# 2_ext_conn.net
KiCad netlist of a schematic drawn in Altium Designer
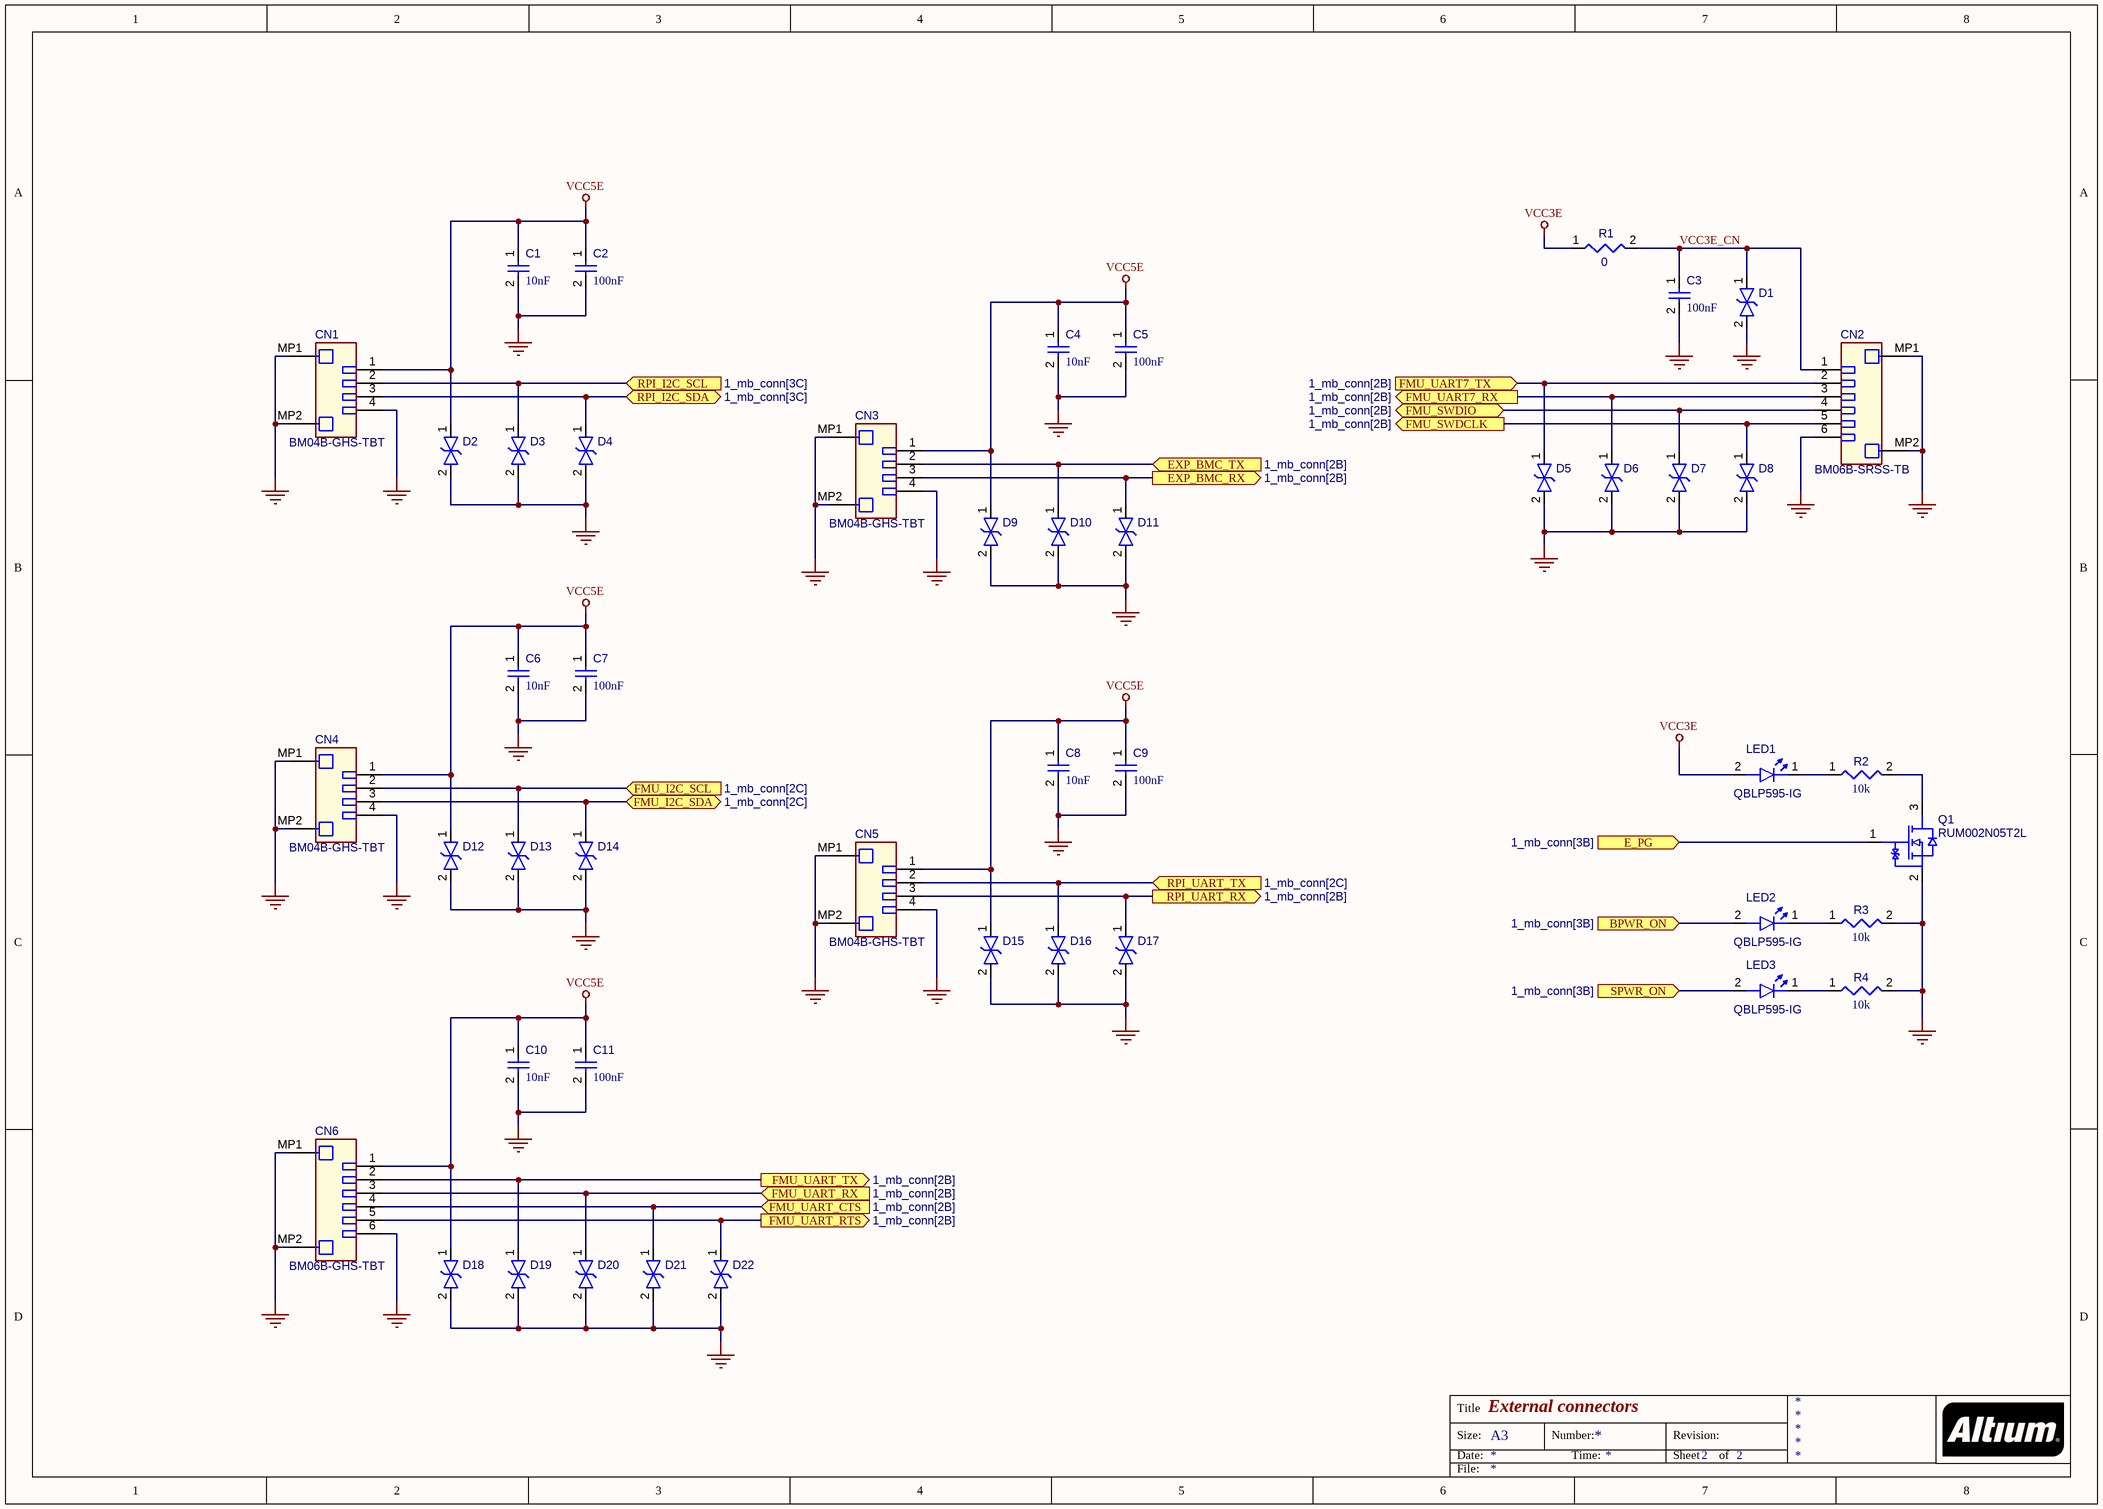
[diagram p0: 2_ext_conn.SchDoc]

(export (version "E")
  (design (tool "Eeschema 10.0.6"))
  (components
    (comp (ref "C1")
      (value "10nF")
      (footprint "CAPC0402(1005)60_L")
      (description "Chip Capacitor, 10nF +/-20%, 50V, 0402, Thickness 0.6 mm")
      (fields (field (name "TOLERANCE") "5%") (field (name "Comment") "Capacitor 10nF +/-20% 50V 0402"))
      (libsource (lib "SKA- Automa玢o de Engenharias") (part "CAP-NP-2"))
    )
    (comp (ref "C2")
      (value "100nF")
      (footprint "CAPC0402(1005)60_L")
      (description "Chip Capacitor, 100nF +/-20%, 10V, 0402, Thickness 0.6 mm")
      (fields (field (name "TOLERANCE") "20%") (field (name "Comment") "Capacitor 100nF +/-20% 10V 0402"))
      (libsource (lib "SKA- Automa玢o de Engenharias") (part "CAP-NP-2"))
    )
    (comp (ref "C3")
      (value "100nF")
      (footprint "CAPC0402(1005)60_L")
      (description "Chip Capacitor, 100nF +/-20%, 10V, 0402, Thickness 0.6 mm")
      (fields (field (name "TOLERANCE") "20%") (field (name "Comment") "Capacitor 100nF +/-20% 10V 0402"))
      (libsource (lib "SKA- Automa玢o de Engenharias") (part "CAP-NP-2"))
    )
    (comp (ref "C4")
      (value "10nF")
      (footprint "CAPC0402(1005)60_L")
      (description "Chip Capacitor, 10nF +/-20%, 50V, 0402, Thickness 0.6 mm")
      (fields (field (name "TOLERANCE") "5%") (field (name "Comment") "Capacitor 10nF +/-20% 50V 0402"))
      (libsource (lib "SKA- Automa玢o de Engenharias") (part "CAP-NP-2"))
    )
    (comp (ref "C5")
      (value "100nF")
      (footprint "CAPC0402(1005)60_L")
      (description "Chip Capacitor, 100nF +/-20%, 10V, 0402, Thickness 0.6 mm")
      (fields (field (name "TOLERANCE") "20%") (field (name "Comment") "Capacitor 100nF +/-20% 10V 0402"))
      (libsource (lib "SKA- Automa玢o de Engenharias") (part "CAP-NP-2"))
    )
    (comp (ref "C6")
      (value "10nF")
      (footprint "CAPC0402(1005)60_L")
      (description "Chip Capacitor, 10nF +/-20%, 50V, 0402, Thickness 0.6 mm")
      (fields (field (name "TOLERANCE") "5%") (field (name "Comment") "Capacitor 10nF +/-20% 50V 0402"))
      (libsource (lib "SKA- Automa玢o de Engenharias") (part "CAP-NP-2"))
    )
    (comp (ref "C7")
      (value "100nF")
      (footprint "CAPC0402(1005)60_L")
      (description "Chip Capacitor, 100nF +/-20%, 10V, 0402, Thickness 0.6 mm")
      (fields (field (name "TOLERANCE") "20%") (field (name "Comment") "Capacitor 100nF +/-20% 10V 0402"))
      (libsource (lib "SKA- Automa玢o de Engenharias") (part "CAP-NP-2"))
    )
    (comp (ref "C8")
      (value "10nF")
      (footprint "CAPC0402(1005)60_L")
      (description "Chip Capacitor, 10nF +/-20%, 50V, 0402, Thickness 0.6 mm")
      (fields (field (name "TOLERANCE") "5%") (field (name "Comment") "Capacitor 10nF +/-20% 50V 0402"))
      (libsource (lib "SKA- Automa玢o de Engenharias") (part "CAP-NP-2"))
    )
    (comp (ref "C9")
      (value "100nF")
      (footprint "CAPC0402(1005)60_L")
      (description "Chip Capacitor, 100nF +/-20%, 10V, 0402, Thickness 0.6 mm")
      (fields (field (name "TOLERANCE") "20%") (field (name "Comment") "Capacitor 100nF +/-20% 10V 0402"))
      (libsource (lib "SKA- Automa玢o de Engenharias") (part "CAP-NP-2"))
    )
    (comp (ref "C10")
      (value "10nF")
      (footprint "CAPC0402(1005)60_L")
      (description "Chip Capacitor, 10nF +/-20%, 50V, 0402, Thickness 0.6 mm")
      (fields (field (name "TOLERANCE") "5%") (field (name "Comment") "Capacitor 10nF +/-20% 50V 0402"))
      (libsource (lib "SKA- Automa玢o de Engenharias") (part "CAP-NP-2"))
    )
    (comp (ref "C11")
      (value "100nF")
      (footprint "CAPC0402(1005)60_L")
      (description "Chip Capacitor, 100nF +/-20%, 10V, 0402, Thickness 0.6 mm")
      (fields (field (name "TOLERANCE") "20%") (field (name "Comment") "Capacitor 100nF +/-20% 10V 0402"))
      (libsource (lib "SKA- Automa玢o de Engenharias") (part "CAP-NP-2"))
    )
    (comp (ref "CN1")
      (value "BM04B-GHS-TBT")
      (footprint "JST-BM04B-GHS-TBT_V")
      (description "Header, Pitch 1.25 mm, 1 x 4 Position, Height 4.05 mm, -25 to 85 degC")
      (libsource (lib "<Company> Server") (part "CMP-00071-3"))
    )
    (comp (ref "CN2")
      (value "BM06B-SRSS-TB")
      (footprint "JST-BM06B-SRSS-TB_V")
      (description "Header, Pitch 1 mm, 1 x 6 Position, Height 4.25 mm, -25 to 85 degC")
      (libsource (lib "") (part "CMP-00143-5_1"))
    )
    (comp (ref "CN3")
      (value "BM04B-GHS-TBT")
      (footprint "JST-BM04B-GHS-TBT_V")
      (description "Header, Pitch 1.25 mm, 1 x 4 Position, Height 4.05 mm, -25 to 85 degC")
      (libsource (lib "<Company> Server") (part "CMP-00071-3"))
    )
    (comp (ref "CN4")
      (value "BM04B-GHS-TBT")
      (footprint "JST-BM04B-GHS-TBT_V")
      (description "Header, Pitch 1.25 mm, 1 x 4 Position, Height 4.05 mm, -25 to 85 degC")
      (libsource (lib "<Company> Server") (part "CMP-00071-3"))
    )
    (comp (ref "CN5")
      (value "BM04B-GHS-TBT")
      (footprint "JST-BM04B-GHS-TBT_V")
      (description "Header, Pitch 1.25 mm, 1 x 4 Position, Height 4.05 mm, -25 to 85 degC")
      (libsource (lib "<Company> Server") (part "CMP-00071-3"))
    )
    (comp (ref "CN6")
      (value "BM06B-GHS-TBT")
      (footprint "JST-BM06B-GHS-TBT_V")
      (description "Header, Pitch 1.25 mm, 1 x 6 Position, Height 4.05 mm, -25 to 85 degC")
      (libsource (lib "<Company> Server") (part "CMP-00143-5"))
    )
    (comp (ref "D1")
      (value "ESDALC5-1BM2")
      (footprint "STM-SOD-882_V")
      (description "Single Line Low Capacitance Transil™, 5 V, -55 to 150 degC, 2-Pin SOD-882, RoHS, Tape and Reel")
      (libsource (lib "<Company> Server") (part "D-TVS-AA-2"))
    )
    (comp (ref "D2")
      (value "ESDALC5-1BM2")
      (footprint "STM-SOD-882_V")
      (description "Single Line Low Capacitance Transil™, 5 V, -55 to 150 degC, 2-Pin SOD-882, RoHS, Tape and Reel")
      (libsource (lib "<Company> Server") (part "D-TVS-AA-2"))
    )
    (comp (ref "D3")
      (value "ESDALC5-1BM2")
      (footprint "STM-SOD-882_V")
      (description "Single Line Low Capacitance Transil™, 5 V, -55 to 150 degC, 2-Pin SOD-882, RoHS, Tape and Reel")
      (libsource (lib "<Company> Server") (part "D-TVS-AA-2"))
    )
    (comp (ref "D4")
      (value "ESDALC5-1BM2")
      (footprint "STM-SOD-882_V")
      (description "Single Line Low Capacitance Transil™, 5 V, -55 to 150 degC, 2-Pin SOD-882, RoHS, Tape and Reel")
      (libsource (lib "<Company> Server") (part "D-TVS-AA-2"))
    )
    (comp (ref "D5")
      (value "ESDALC5-1BM2")
      (footprint "STM-SOD-882_V")
      (description "Single Line Low Capacitance Transil™, 5 V, -55 to 150 degC, 2-Pin SOD-882, RoHS, Tape and Reel")
      (libsource (lib "<Company> Server") (part "D-TVS-AA-2"))
    )
    (comp (ref "D6")
      (value "ESDALC5-1BM2")
      (footprint "STM-SOD-882_V")
      (description "Single Line Low Capacitance Transil™, 5 V, -55 to 150 degC, 2-Pin SOD-882, RoHS, Tape and Reel")
      (libsource (lib "<Company> Server") (part "D-TVS-AA-2"))
    )
    (comp (ref "D7")
      (value "ESDALC5-1BM2")
      (footprint "STM-SOD-882_V")
      (description "Single Line Low Capacitance Transil™, 5 V, -55 to 150 degC, 2-Pin SOD-882, RoHS, Tape and Reel")
      (libsource (lib "<Company> Server") (part "D-TVS-AA-2"))
    )
    (comp (ref "D8")
      (value "ESDALC5-1BM2")
      (footprint "STM-SOD-882_V")
      (description "Single Line Low Capacitance Transil™, 5 V, -55 to 150 degC, 2-Pin SOD-882, RoHS, Tape and Reel")
      (libsource (lib "<Company> Server") (part "D-TVS-AA-2"))
    )
    (comp (ref "D9")
      (value "ESDALC5-1BM2")
      (footprint "STM-SOD-882_V")
      (description "Single Line Low Capacitance Transil™, 5 V, -55 to 150 degC, 2-Pin SOD-882, RoHS, Tape and Reel")
      (libsource (lib "<Company> Server") (part "D-TVS-AA-2"))
    )
    (comp (ref "D10")
      (value "ESDALC5-1BM2")
      (footprint "STM-SOD-882_V")
      (description "Single Line Low Capacitance Transil™, 5 V, -55 to 150 degC, 2-Pin SOD-882, RoHS, Tape and Reel")
      (libsource (lib "<Company> Server") (part "D-TVS-AA-2"))
    )
    (comp (ref "D11")
      (value "ESDALC5-1BM2")
      (footprint "STM-SOD-882_V")
      (description "Single Line Low Capacitance Transil™, 5 V, -55 to 150 degC, 2-Pin SOD-882, RoHS, Tape and Reel")
      (libsource (lib "<Company> Server") (part "D-TVS-AA-2"))
    )
    (comp (ref "D12")
      (value "ESDALC5-1BM2")
      (footprint "STM-SOD-882_V")
      (description "Single Line Low Capacitance Transil™, 5 V, -55 to 150 degC, 2-Pin SOD-882, RoHS, Tape and Reel")
      (libsource (lib "<Company> Server") (part "D-TVS-AA-2"))
    )
    (comp (ref "D13")
      (value "ESDALC5-1BM2")
      (footprint "STM-SOD-882_V")
      (description "Single Line Low Capacitance Transil™, 5 V, -55 to 150 degC, 2-Pin SOD-882, RoHS, Tape and Reel")
      (libsource (lib "<Company> Server") (part "D-TVS-AA-2"))
    )
    (comp (ref "D14")
      (value "ESDALC5-1BM2")
      (footprint "STM-SOD-882_V")
      (description "Single Line Low Capacitance Transil™, 5 V, -55 to 150 degC, 2-Pin SOD-882, RoHS, Tape and Reel")
      (libsource (lib "<Company> Server") (part "D-TVS-AA-2"))
    )
    (comp (ref "D15")
      (value "ESDALC5-1BM2")
      (footprint "STM-SOD-882_V")
      (description "Single Line Low Capacitance Transil™, 5 V, -55 to 150 degC, 2-Pin SOD-882, RoHS, Tape and Reel")
      (libsource (lib "<Company> Server") (part "D-TVS-AA-2"))
    )
    (comp (ref "D16")
      (value "ESDALC5-1BM2")
      (footprint "STM-SOD-882_V")
      (description "Single Line Low Capacitance Transil™, 5 V, -55 to 150 degC, 2-Pin SOD-882, RoHS, Tape and Reel")
      (libsource (lib "<Company> Server") (part "D-TVS-AA-2"))
    )
    (comp (ref "D17")
      (value "ESDALC5-1BM2")
      (footprint "STM-SOD-882_V")
      (description "Single Line Low Capacitance Transil™, 5 V, -55 to 150 degC, 2-Pin SOD-882, RoHS, Tape and Reel")
      (libsource (lib "<Company> Server") (part "D-TVS-AA-2"))
    )
    (comp (ref "D18")
      (value "ESDALC5-1BM2")
      (footprint "STM-SOD-882_V")
      (description "Single Line Low Capacitance Transil™, 5 V, -55 to 150 degC, 2-Pin SOD-882, RoHS, Tape and Reel")
      (libsource (lib "<Company> Server") (part "D-TVS-AA-2"))
    )
    (comp (ref "D19")
      (value "ESDALC5-1BM2")
      (footprint "STM-SOD-882_V")
      (description "Single Line Low Capacitance Transil™, 5 V, -55 to 150 degC, 2-Pin SOD-882, RoHS, Tape and Reel")
      (libsource (lib "<Company> Server") (part "D-TVS-AA-2"))
    )
    (comp (ref "D20")
      (value "ESDALC5-1BM2")
      (footprint "STM-SOD-882_V")
      (description "Single Line Low Capacitance Transil™, 5 V, -55 to 150 degC, 2-Pin SOD-882, RoHS, Tape and Reel")
      (libsource (lib "<Company> Server") (part "D-TVS-AA-2"))
    )
    (comp (ref "D21")
      (value "ESDALC5-1BM2")
      (footprint "STM-SOD-882_V")
      (description "Single Line Low Capacitance Transil™, 5 V, -55 to 150 degC, 2-Pin SOD-882, RoHS, Tape and Reel")
      (libsource (lib "<Company> Server") (part "D-TVS-AA-2"))
    )
    (comp (ref "D22")
      (value "ESDALC5-1BM2")
      (footprint "STM-SOD-882_V")
      (description "Single Line Low Capacitance Transil™, 5 V, -55 to 150 degC, 2-Pin SOD-882, RoHS, Tape and Reel")
      (libsource (lib "<Company> Server") (part "D-TVS-AA-2"))
    )
    (comp (ref "LED1")
      (value "QBLP595-IG")
      (footprint "QTB-QBLP595_V")
      (description "Chip LED 0402, Green, 0.02 A, 3.1 to 3.7 V, -40 to 80 degC, 2-Pin SMD, RoHS, Tape and Reel")
      (libsource (lib "<Company> Server") (part "LED-KA-2"))
    )
    (comp (ref "LED2")
      (value "QBLP595-IG")
      (footprint "QTB-QBLP595_V")
      (description "Chip LED 0402, Green, 0.02 A, 3.1 to 3.7 V, -40 to 80 degC, 2-Pin SMD, RoHS, Tape and Reel")
      (libsource (lib "<Company> Server") (part "LED-KA-2"))
    )
    (comp (ref "LED3")
      (value "QBLP595-IG")
      (footprint "QTB-QBLP595_V")
      (description "Chip LED 0402, Green, 0.02 A, 3.1 to 3.7 V, -40 to 80 degC, 2-Pin SMD, RoHS, Tape and Reel")
      (libsource (lib "<Company> Server") (part "LED-KA-2"))
    )
    (comp (ref "Q1")
      (value "RUM002N05T2L")
      (footprint "ROHM-SOT723-3_V")
      (description "Nch Small Signal MOSFET, 50 V, 200 mA, 3-Pin SOT723, RoHS, Tape and Reel")
      (libsource (lib "<Company> Server") (part "CMP-00005-6"))
    )
    (comp (ref "R1")
      (value "0")
      (footprint "RESC0603(1608)_L")
      (description "Jumper 0603")
      (libsource (lib "<Company> Server") (part "RES-2"))
    )
    (comp (ref "R2")
      (value "10k")
      (footprint "RESC0402(1005)_L")
      (description "Chip Resistor, 10 kOhms, +/-1 %, 63 mW, -55 to 125 degC, 0402")
      (fields (field (name "TOLERANCE") "1%") (field (name "POWER") "63mW"))
      (libsource (lib "SKA- Automa玢o de Engenharias") (part "RES-2"))
    )
    (comp (ref "R3")
      (value "10k")
      (footprint "RESC0402(1005)_L")
      (description "Chip Resistor, 10 kOhms, +/-1 %, 63 mW, -55 to 125 degC, 0402")
      (fields (field (name "TOLERANCE") "1%") (field (name "POWER") "63mW"))
      (libsource (lib "SKA- Automa玢o de Engenharias") (part "RES-2"))
    )
    (comp (ref "R4")
      (value "10k")
      (footprint "RESC0402(1005)_L")
      (description "Chip Resistor, 10 kOhms, +/-1 %, 63 mW, -55 to 125 degC, 0402")
      (fields (field (name "TOLERANCE") "1%") (field (name "POWER") "63mW"))
      (libsource (lib "SKA- Automa玢o de Engenharias") (part "RES-2"))
    )
  )
  (nets
    (net (code "1") (name "/BPWR_ON") (class "Default")
      (node (ref "LED2") (pin "2") (pinfunction "A_2") (pintype "passive"))
    )
    (net (code "2") (name "/EXP_BMC_RX") (class "Default")
      (node (ref "CN3") (pin "3") (pinfunction "3_3") (pintype "passive"))
      (node (ref "D11") (pin "1") (pinfunction "A_1") (pintype "passive"))
    )
    (net (code "3") (name "/EXP_BMC_TX") (class "Default")
      (node (ref "CN3") (pin "2") (pinfunction "2_2") (pintype "passive"))
      (node (ref "D10") (pin "1") (pinfunction "A_1") (pintype "passive"))
    )
    (net (code "4") (name "/E_PG") (class "Default")
      (node (ref "Q1") (pin "1") (pinfunction "G_1") (pintype "passive"))
    )
    (net (code "5") (name "/FMU_I2C_SCL") (class "Default")
      (node (ref "CN4") (pin "2") (pinfunction "2_2") (pintype "passive"))
      (node (ref "D13") (pin "1") (pinfunction "A_1") (pintype "passive"))
    )
    (net (code "6") (name "/FMU_I2C_SDA") (class "Default")
      (node (ref "CN4") (pin "3") (pinfunction "3_3") (pintype "passive"))
      (node (ref "D14") (pin "1") (pinfunction "A_1") (pintype "passive"))
    )
    (net (code "7") (name "/FMU_SWDCLK") (class "Default")
      (node (ref "CN2") (pin "5") (pinfunction "5_5") (pintype "passive"))
      (node (ref "D8") (pin "1") (pinfunction "A_1") (pintype "passive"))
    )
    (net (code "8") (name "/FMU_SWDIO") (class "Default")
      (node (ref "CN2") (pin "4") (pinfunction "4_4") (pintype "passive"))
      (node (ref "D7") (pin "1") (pinfunction "A_1") (pintype "passive"))
    )
    (net (code "9") (name "/FMU_UART7_RX") (class "Default")
      (node (ref "CN2") (pin "3") (pinfunction "3_3") (pintype "passive"))
      (node (ref "D6") (pin "1") (pinfunction "A_1") (pintype "passive"))
    )
    (net (code "10") (name "/FMU_UART7_TX") (class "Default")
      (node (ref "CN2") (pin "2") (pinfunction "2_2") (pintype "passive"))
      (node (ref "D5") (pin "1") (pinfunction "A_1") (pintype "passive"))
    )
    (net (code "11") (name "/FMU_UART_CTS") (class "Default")
      (node (ref "CN6") (pin "4") (pinfunction "4_4") (pintype "passive"))
      (node (ref "D21") (pin "1") (pinfunction "A_1") (pintype "passive"))
    )
    (net (code "12") (name "/FMU_UART_RTS") (class "Default")
      (node (ref "CN6") (pin "5") (pinfunction "5_5") (pintype "passive"))
      (node (ref "D22") (pin "1") (pinfunction "A_1") (pintype "passive"))
    )
    (net (code "13") (name "/FMU_UART_RX") (class "Default")
      (node (ref "CN6") (pin "3") (pinfunction "3_3") (pintype "passive"))
      (node (ref "D20") (pin "1") (pinfunction "A_1") (pintype "passive"))
    )
    (net (code "14") (name "/FMU_UART_TX") (class "Default")
      (node (ref "CN6") (pin "2") (pinfunction "2_2") (pintype "passive"))
      (node (ref "D19") (pin "1") (pinfunction "A_1") (pintype "passive"))
    )
    (net (code "15") (name "/RPI_I2C_SCL") (class "Default")
      (node (ref "CN1") (pin "2") (pinfunction "2_2") (pintype "passive"))
      (node (ref "D3") (pin "1") (pinfunction "A_1") (pintype "passive"))
    )
    (net (code "16") (name "/RPI_I2C_SDA") (class "Default")
      (node (ref "CN1") (pin "3") (pinfunction "3_3") (pintype "passive"))
      (node (ref "D4") (pin "1") (pinfunction "A_1") (pintype "passive"))
    )
    (net (code "17") (name "/RPI_UART_RX") (class "Default")
      (node (ref "CN5") (pin "3") (pinfunction "3_3") (pintype "passive"))
      (node (ref "D17") (pin "1") (pinfunction "A_1") (pintype "passive"))
    )
    (net (code "18") (name "/RPI_UART_TX") (class "Default")
      (node (ref "CN5") (pin "2") (pinfunction "2_2") (pintype "passive"))
      (node (ref "D16") (pin "1") (pinfunction "A_1") (pintype "passive"))
    )
    (net (code "19") (name "/SPWR_ON") (class "Default")
      (node (ref "LED3") (pin "2") (pinfunction "A_2") (pintype "passive"))
    )
    (net (code "20") (name "/VCC3E_CN") (class "Default")
      (node (ref "C3") (pin "1") (pinfunction "1_1") (pintype "passive"))
      (node (ref "CN2") (pin "1") (pinfunction "1_1") (pintype "passive"))
      (node (ref "D1") (pin "1") (pinfunction "A_1") (pintype "passive"))
      (node (ref "R1") (pin "2") (pinfunction "2_2") (pintype "passive"))
    )
    (net (code "21") (name "GND") (class "Default")
      (node (ref "C1") (pin "2") (pinfunction "2_2") (pintype "passive"))
      (node (ref "C10") (pin "2") (pinfunction "2_2") (pintype "passive"))
      (node (ref "C11") (pin "2") (pinfunction "2_2") (pintype "passive"))
      (node (ref "C2") (pin "2") (pinfunction "2_2") (pintype "passive"))
      (node (ref "C3") (pin "2") (pinfunction "2_2") (pintype "passive"))
      (node (ref "C4") (pin "2") (pinfunction "2_2") (pintype "passive"))
      (node (ref "C5") (pin "2") (pinfunction "2_2") (pintype "passive"))
      (node (ref "C6") (pin "2") (pinfunction "2_2") (pintype "passive"))
      (node (ref "C7") (pin "2") (pinfunction "2_2") (pintype "passive"))
      (node (ref "C8") (pin "2") (pinfunction "2_2") (pintype "passive"))
      (node (ref "C9") (pin "2") (pinfunction "2_2") (pintype "passive"))
      (node (ref "CN1") (pin "4") (pinfunction "4_4") (pintype "passive"))
      (node (ref "CN1") (pin "MP1") (pinfunction "MP1_MP1") (pintype "passive"))
      (node (ref "CN1") (pin "MP2") (pinfunction "MP2_MP2") (pintype "passive"))
      (node (ref "CN2") (pin "6") (pinfunction "6_6") (pintype "passive"))
      (node (ref "CN2") (pin "MP1") (pinfunction "MP1_MP1") (pintype "passive"))
      (node (ref "CN2") (pin "MP2") (pinfunction "MP2_MP2") (pintype "passive"))
      (node (ref "CN3") (pin "4") (pinfunction "4_4") (pintype "passive"))
      (node (ref "CN3") (pin "MP1") (pinfunction "MP1_MP1") (pintype "passive"))
      (node (ref "CN3") (pin "MP2") (pinfunction "MP2_MP2") (pintype "passive"))
      (node (ref "CN4") (pin "4") (pinfunction "4_4") (pintype "passive"))
      (node (ref "CN4") (pin "MP1") (pinfunction "MP1_MP1") (pintype "passive"))
      (node (ref "CN4") (pin "MP2") (pinfunction "MP2_MP2") (pintype "passive"))
      (node (ref "CN5") (pin "4") (pinfunction "4_4") (pintype "passive"))
      (node (ref "CN5") (pin "MP1") (pinfunction "MP1_MP1") (pintype "passive"))
      (node (ref "CN5") (pin "MP2") (pinfunction "MP2_MP2") (pintype "passive"))
      (node (ref "CN6") (pin "6") (pinfunction "6_6") (pintype "passive"))
      (node (ref "CN6") (pin "MP1") (pinfunction "MP1_MP1") (pintype "passive"))
      (node (ref "CN6") (pin "MP2") (pinfunction "MP2_MP2") (pintype "passive"))
      (node (ref "D1") (pin "2") (pinfunction "A_2") (pintype "passive"))
      (node (ref "D10") (pin "2") (pinfunction "A_2") (pintype "passive"))
      (node (ref "D11") (pin "2") (pinfunction "A_2") (pintype "passive"))
      (node (ref "D12") (pin "2") (pinfunction "A_2") (pintype "passive"))
      (node (ref "D13") (pin "2") (pinfunction "A_2") (pintype "passive"))
      (node (ref "D14") (pin "2") (pinfunction "A_2") (pintype "passive"))
      (node (ref "D15") (pin "2") (pinfunction "A_2") (pintype "passive"))
      (node (ref "D16") (pin "2") (pinfunction "A_2") (pintype "passive"))
      (node (ref "D17") (pin "2") (pinfunction "A_2") (pintype "passive"))
      (node (ref "D18") (pin "2") (pinfunction "A_2") (pintype "passive"))
      (node (ref "D19") (pin "2") (pinfunction "A_2") (pintype "passive"))
      (node (ref "D2") (pin "2") (pinfunction "A_2") (pintype "passive"))
      (node (ref "D20") (pin "2") (pinfunction "A_2") (pintype "passive"))
      (node (ref "D21") (pin "2") (pinfunction "A_2") (pintype "passive"))
      (node (ref "D22") (pin "2") (pinfunction "A_2") (pintype "passive"))
      (node (ref "D3") (pin "2") (pinfunction "A_2") (pintype "passive"))
      (node (ref "D4") (pin "2") (pinfunction "A_2") (pintype "passive"))
      (node (ref "D5") (pin "2") (pinfunction "A_2") (pintype "passive"))
      (node (ref "D6") (pin "2") (pinfunction "A_2") (pintype "passive"))
      (node (ref "D7") (pin "2") (pinfunction "A_2") (pintype "passive"))
      (node (ref "D8") (pin "2") (pinfunction "A_2") (pintype "passive"))
      (node (ref "D9") (pin "2") (pinfunction "A_2") (pintype "passive"))
      (node (ref "Q1") (pin "2") (pinfunction "S_2") (pintype "passive"))
      (node (ref "R3") (pin "2") (pinfunction "2_2") (pintype "passive"))
      (node (ref "R4") (pin "2") (pinfunction "2_2") (pintype "passive"))
    )
    (net (code "22") (name "Net-(LED1-K)") (class "Default")
      (node (ref "LED1") (pin "1") (pinfunction "K_1") (pintype "passive"))
      (node (ref "R2") (pin "1") (pinfunction "1_1") (pintype "passive"))
    )
    (net (code "23") (name "Net-(LED2-K)") (class "Default")
      (node (ref "LED2") (pin "1") (pinfunction "K_1") (pintype "passive"))
      (node (ref "R3") (pin "1") (pinfunction "1_1") (pintype "passive"))
    )
    (net (code "24") (name "Net-(LED3-K)") (class "Default")
      (node (ref "LED3") (pin "1") (pinfunction "K_1") (pintype "passive"))
      (node (ref "R4") (pin "1") (pinfunction "1_1") (pintype "passive"))
    )
    (net (code "25") (name "Net-(Q1-D)") (class "Default")
      (node (ref "Q1") (pin "3") (pinfunction "D_3") (pintype "passive"))
      (node (ref "R2") (pin "2") (pinfunction "2_2") (pintype "passive"))
    )
    (net (code "26") (name "VCC3E") (class "Default")
      (node (ref "LED1") (pin "2") (pinfunction "A_2") (pintype "passive"))
      (node (ref "R1") (pin "1") (pinfunction "1_1") (pintype "passive"))
    )
    (net (code "27") (name "VCC5E") (class "Default")
      (node (ref "C1") (pin "1") (pinfunction "1_1") (pintype "passive"))
      (node (ref "C10") (pin "1") (pinfunction "1_1") (pintype "passive"))
      (node (ref "C11") (pin "1") (pinfunction "1_1") (pintype "passive"))
      (node (ref "C2") (pin "1") (pinfunction "1_1") (pintype "passive"))
      (node (ref "C4") (pin "1") (pinfunction "1_1") (pintype "passive"))
      (node (ref "C5") (pin "1") (pinfunction "1_1") (pintype "passive"))
      (node (ref "C6") (pin "1") (pinfunction "1_1") (pintype "passive"))
      (node (ref "C7") (pin "1") (pinfunction "1_1") (pintype "passive"))
      (node (ref "C8") (pin "1") (pinfunction "1_1") (pintype "passive"))
      (node (ref "C9") (pin "1") (pinfunction "1_1") (pintype "passive"))
      (node (ref "CN1") (pin "1") (pinfunction "1_1") (pintype "passive"))
      (node (ref "CN3") (pin "1") (pinfunction "1_1") (pintype "passive"))
      (node (ref "CN4") (pin "1") (pinfunction "1_1") (pintype "passive"))
      (node (ref "CN5") (pin "1") (pinfunction "1_1") (pintype "passive"))
      (node (ref "CN6") (pin "1") (pinfunction "1_1") (pintype "passive"))
      (node (ref "D12") (pin "1") (pinfunction "A_1") (pintype "passive"))
      (node (ref "D15") (pin "1") (pinfunction "A_1") (pintype "passive"))
      (node (ref "D18") (pin "1") (pinfunction "A_1") (pintype "passive"))
      (node (ref "D2") (pin "1") (pinfunction "A_1") (pintype "passive"))
      (node (ref "D9") (pin "1") (pinfunction "A_1") (pintype "passive"))
    )
  )
)
